# SCH_CarAccessoryKitV1_0_2024-07-24.net
KiCad netlist of a schematic drawn in EasyEDA
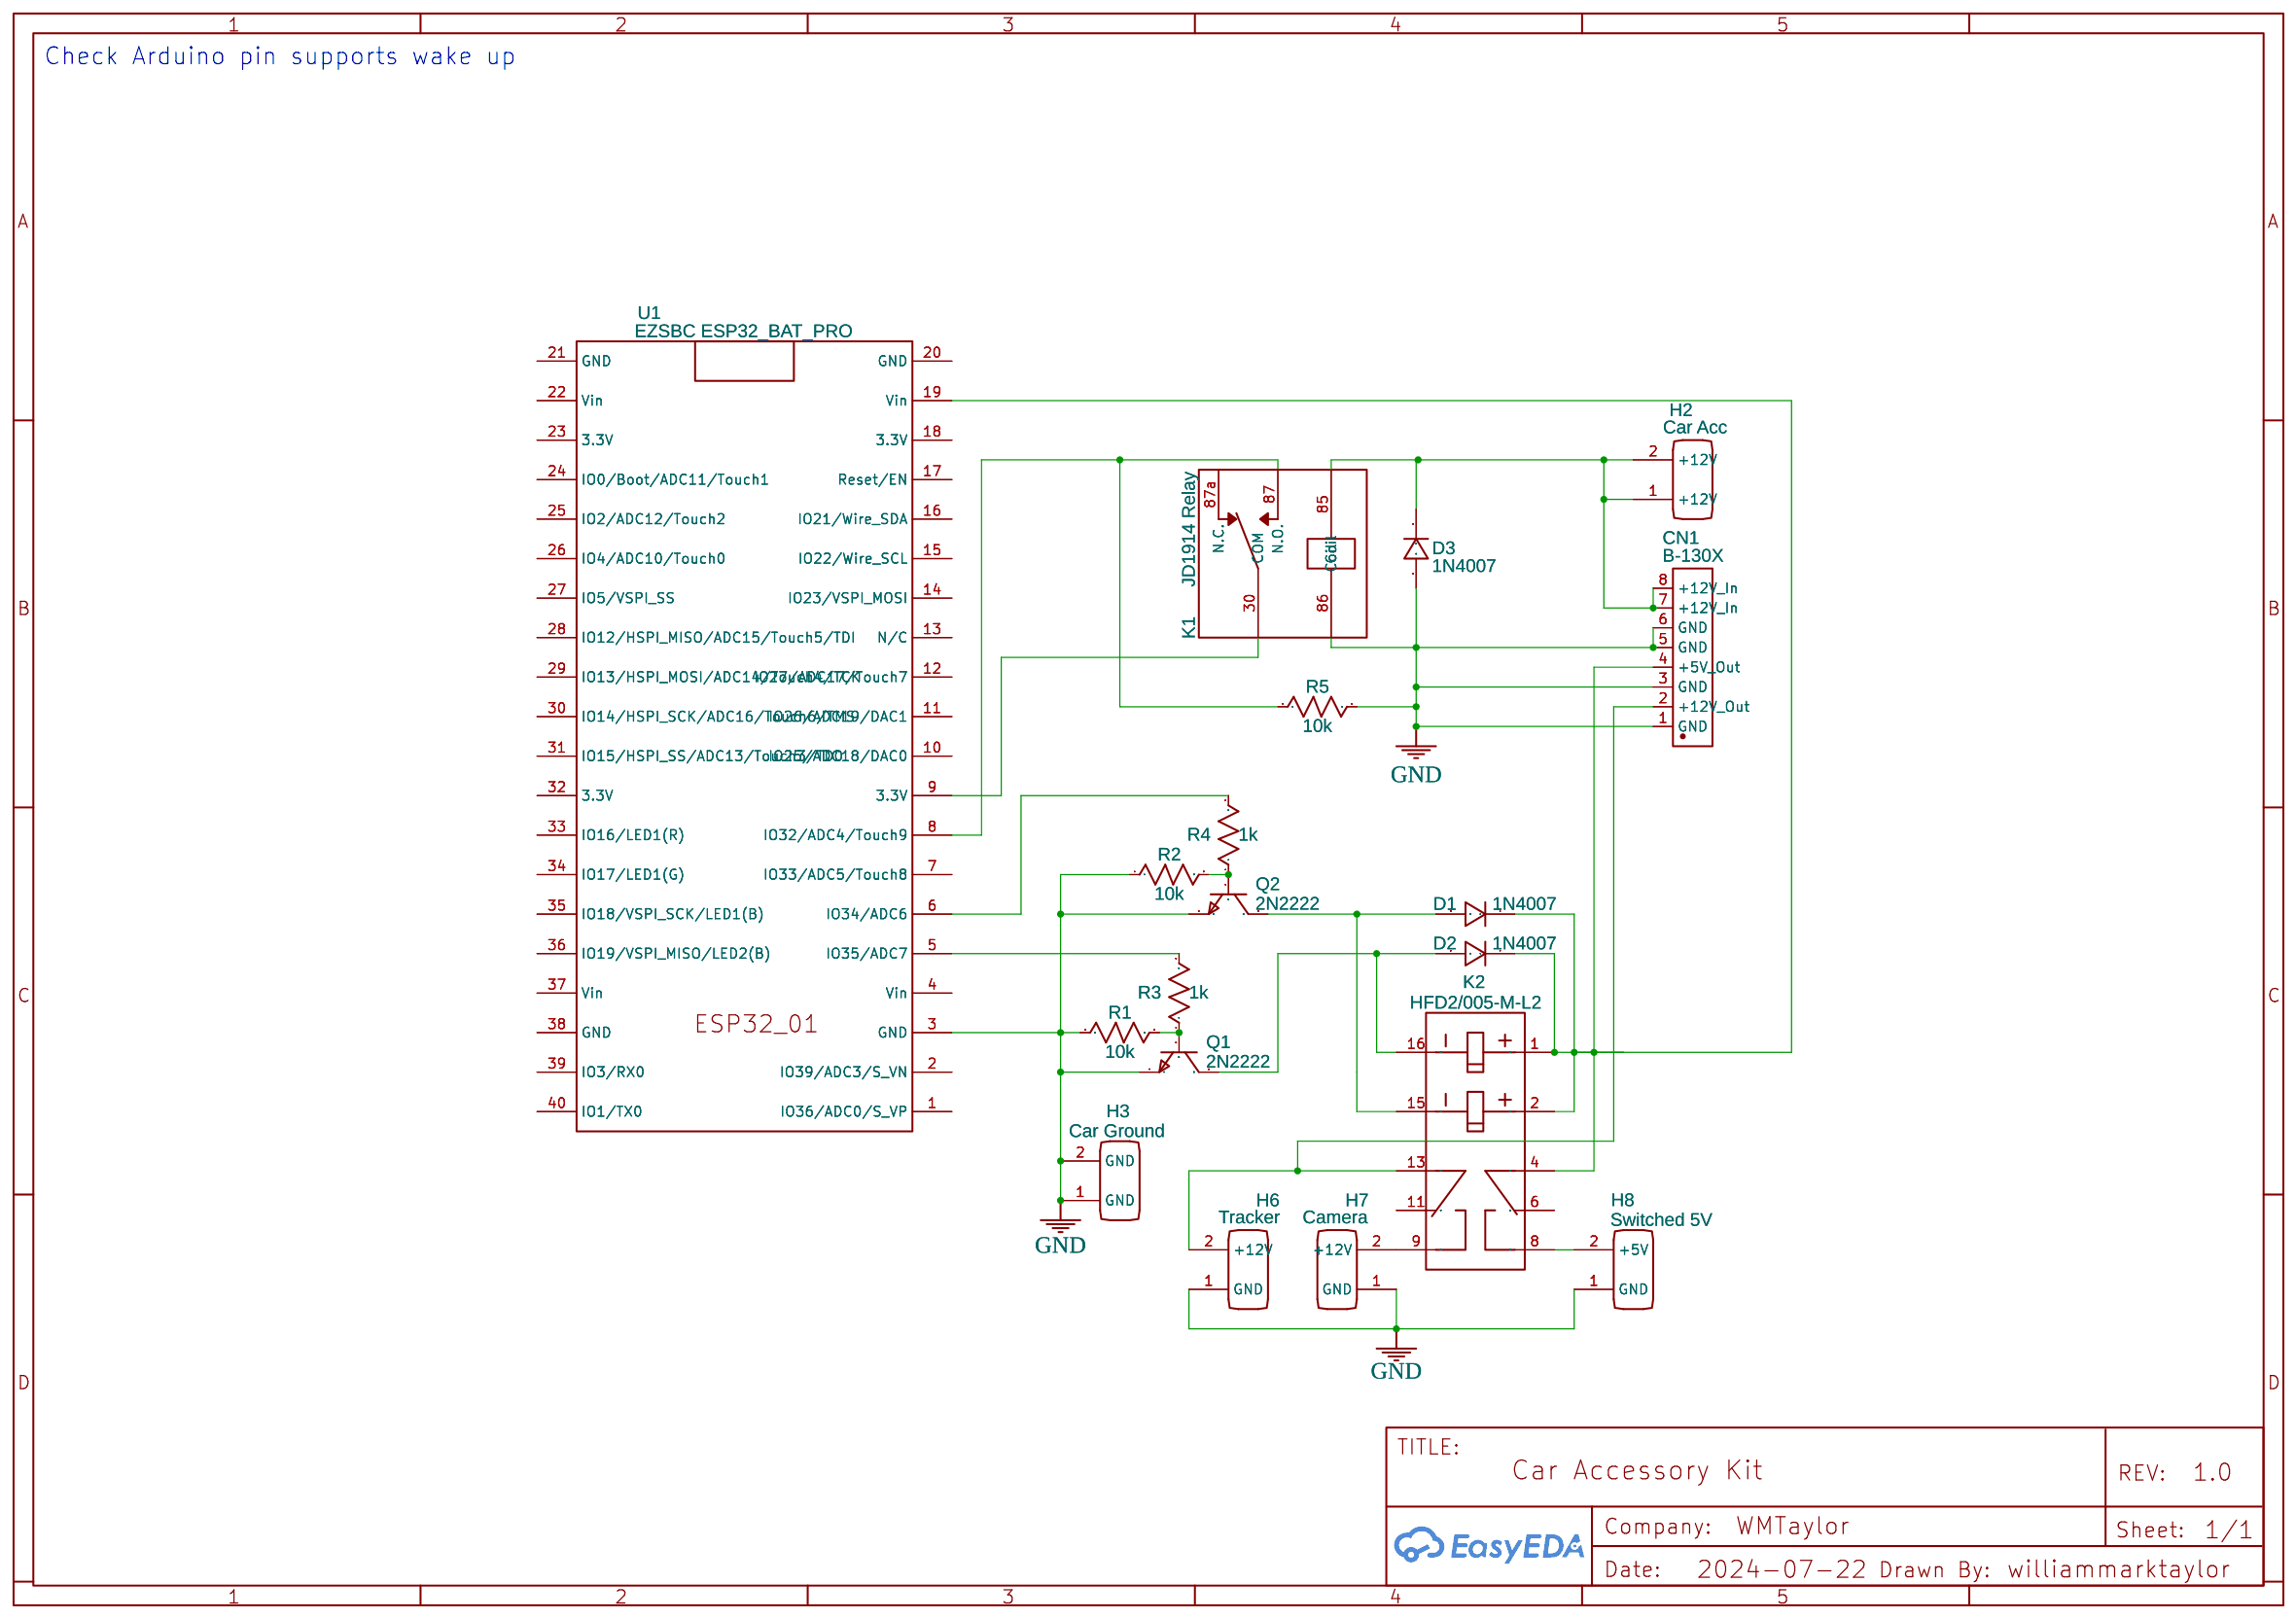
[diagram p0: schematic sheet]

(export (version "E")
  (design (tool "Eeschema 10.0.6"))
  (components
    (comp (ref "CN1")
      (value "B-130X")
      (fields (field (name "Manufacturer Part") "CH3.96-8A") (field (name "Manufacturer") "BOOMELE"))
      (libsource (lib "") (part "CH3.96-8A"))
    )
    (comp (ref "D1")
      (value "1N4007")
      (fields (field (name "Manufacturer") "SEMTECH"))
      (libsource (lib "") (part "1N4007"))
    )
    (comp (ref "D2")
      (value "1N4007")
      (fields (field (name "Manufacturer") "SEMTECH"))
      (libsource (lib "") (part "1N4007"))
    )
    (comp (ref "D3")
      (value "1N4007")
      (fields (field (name "Manufacturer") "SEMTECH"))
      (libsource (lib "") (part "1N4007_1"))
    )
    (comp (ref "H2") (value "Car Acc") (libsource (lib "") (part "JST_VH-2P-3.96")))
    (comp (ref "H3") (value "Car Ground") (libsource (lib "") (part "JST_VH-2P-3.96_1")))
    (comp (ref "H6") (value "Tracker") (libsource (lib "") (part "JST_VH-2P-3.96_3")))
    (comp (ref "H7") (value "Camera") (libsource (lib "") (part "JST_VH-2P-3.96_4")))
    (comp (ref "H8") (value "Switched 5V") (libsource (lib "") (part "JST_VH-2P-3.96_2")))
    (comp (ref "K1")
      (value "JD1914 Relay")
      (fields (field (name "Manufacturer Part") "JD1914") (field (name "Manufacturer") "BenFeng"))
      (libsource (lib "") (part "RELAY JD1914 12V 80A"))
    )
    (comp (ref "K2")
      (value "HFD2/005-M-L2")
      (fields (field (name "Manufacturer") "HF(宏发)"))
      (libsource (lib "") (part "HFD2/005-M-L2"))
    )
    (comp (ref "Q1") (value "2N2222") (libsource (lib "") (part "2N2222")))
    (comp (ref "Q2") (value "2N2222") (libsource (lib "") (part "2N2222")))
    (comp (ref "R1") (value "10k") (libsource (lib "") (part "R_AXIAL-0.3_US")))
    (comp (ref "R2") (value "10k") (libsource (lib "") (part "R_AXIAL-0.3_US")))
    (comp (ref "R3") (value "1k") (libsource (lib "") (part "R_AXIAL-0.3_US_1")))
    (comp (ref "R4") (value "1k") (libsource (lib "") (part "R_AXIAL-0.3_US_1")))
    (comp (ref "R5") (value "10k") (libsource (lib "") (part "R_AXIAL-0.3_US")))
    (comp (ref "U1")
      (value "EZSBC ESP32_BAT_PRO")
      (fields (field (name "Manufacturer Part") "ESP32_01") (field (name "Manufacturer") "EZSBC"))
      (libsource (lib "") (part "EZSBC ESP32_01"))
    )
  )
  (nets
    (net (code "1") (name "GND") (class "Default")
      (node (ref "CN1") (pin "1") (pinfunction "GND_1") (pintype "unspecified"))
      (node (ref "CN1") (pin "3") (pinfunction "GND_3") (pintype "unspecified"))
      (node (ref "CN1") (pin "5") (pinfunction "GND_5") (pintype "unspecified"))
      (node (ref "CN1") (pin "6") (pinfunction "GND_6") (pintype "unspecified"))
      (node (ref "D3") (pin "2") (pinfunction "2_2") (pintype "unspecified"))
      (node (ref "H3") (pin "1") (pinfunction "GND_1") (pintype "unspecified"))
      (node (ref "H3") (pin "2") (pinfunction "GND_2") (pintype "unspecified"))
      (node (ref "H6") (pin "1") (pinfunction "GND_1") (pintype "unspecified"))
      (node (ref "H7") (pin "1") (pinfunction "GND_1") (pintype "unspecified"))
      (node (ref "H8") (pin "1") (pinfunction "GND_1") (pintype "unspecified"))
      (node (ref "K1") (pin "86") (pinfunction "Coil_86") (pintype "unspecified"))
      (node (ref "Q1") (pin "1") (pinfunction "E_1") (pintype "unspecified"))
      (node (ref "Q2") (pin "1") (pinfunction "E_1") (pintype "unspecified"))
      (node (ref "R1") (pin "1") (pinfunction "1_1") (pintype "unspecified"))
      (node (ref "R2") (pin "1") (pinfunction "1_1") (pintype "unspecified"))
      (node (ref "R5") (pin "2") (pinfunction "2_2") (pintype "unspecified"))
      (node (ref "U1") (pin "3") (pinfunction "GND_3") (pintype "unspecified"))
    )
    (net (code "2") (name "Net-(CN1-+5V_Out)") (class "Default")
      (node (ref "CN1") (pin "4") (pinfunction "+5V_Out_4") (pintype "unspecified"))
      (node (ref "D1") (pin "1") (pinfunction "1_1") (pintype "unspecified"))
      (node (ref "D2") (pin "1") (pinfunction "1_1") (pintype "unspecified"))
      (node (ref "K2") (pin "1") (pinfunction "1_1") (pintype "unspecified"))
      (node (ref "K2") (pin "2") (pinfunction "2_2") (pintype "unspecified"))
      (node (ref "K2") (pin "4") (pinfunction "4_4") (pintype "unspecified"))
      (node (ref "U1") (pin "19") (pinfunction "Vin_19") (pintype "unspecified"))
    )
    (net (code "3") (name "Net-(CN1-+12V_In-Pad7)") (class "Default")
      (node (ref "CN1") (pin "7") (pinfunction "+12V_In_7") (pintype "unspecified"))
      (node (ref "CN1") (pin "8") (pinfunction "+12V_In_8") (pintype "unspecified"))
      (node (ref "D3") (pin "1") (pinfunction "1_1") (pintype "unspecified"))
      (node (ref "H2") (pin "1") (pinfunction "+12V_1") (pintype "unspecified"))
      (node (ref "H2") (pin "2") (pinfunction "+12V_2") (pintype "unspecified"))
      (node (ref "K1") (pin "85") (pinfunction "Coil_85") (pintype "unspecified"))
    )
    (net (code "4") (name "Net-(CN1-+12V_Out)") (class "Default")
      (node (ref "CN1") (pin "2") (pinfunction "+12V_Out_2") (pintype "unspecified"))
      (node (ref "H6") (pin "2") (pinfunction "+12V_2") (pintype "unspecified"))
      (node (ref "K2") (pin "13") (pinfunction "13_13") (pintype "unspecified"))
    )
    (net (code "5") (name "Net-(H7-+12V)") (class "Default")
      (node (ref "H7") (pin "2") (pinfunction "+12V_2") (pintype "unspecified"))
      (node (ref "K2") (pin "9") (pinfunction "9_9") (pintype "unspecified"))
    )
    (net (code "6") (name "Net-(H8-+5V)") (class "Default")
      (node (ref "H8") (pin "2") (pinfunction "+5V_2") (pintype "unspecified"))
      (node (ref "K2") (pin "8") (pinfunction "8_8") (pintype "unspecified"))
    )
    (net (code "7") (name "Net-(K1-COM)") (class "Default")
      (node (ref "K1") (pin "30") (pinfunction "COM_30") (pintype "unspecified"))
      (node (ref "U1") (pin "9") (pinfunction "3.3V_9") (pintype "unspecified"))
    )
    (net (code "8") (name "Net-(K1-N.O.)") (class "Default")
      (node (ref "K1") (pin "87") (pinfunction "N.O._87") (pintype "unspecified"))
      (node (ref "R5") (pin "1") (pinfunction "1_1") (pintype "unspecified"))
      (node (ref "U1") (pin "8") (pinfunction "IO32/ADC4/Touch9_8") (pintype "unspecified"))
    )
    (net (code "9") (name "Net-(Q1-B)") (class "Default")
      (node (ref "Q1") (pin "2") (pinfunction "B_2") (pintype "unspecified"))
      (node (ref "R1") (pin "2") (pinfunction "2_2") (pintype "unspecified"))
      (node (ref "R3") (pin "1") (pinfunction "1_1") (pintype "unspecified"))
    )
    (net (code "10") (name "Net-(Q1-C)") (class "Default")
      (node (ref "D2") (pin "2") (pinfunction "2_2") (pintype "unspecified"))
      (node (ref "K2") (pin "16") (pinfunction "16_16") (pintype "unspecified"))
      (node (ref "Q1") (pin "3") (pinfunction "C_3") (pintype "unspecified"))
    )
    (net (code "11") (name "Net-(Q2-B)") (class "Default")
      (node (ref "Q2") (pin "2") (pinfunction "B_2") (pintype "unspecified"))
      (node (ref "R2") (pin "2") (pinfunction "2_2") (pintype "unspecified"))
      (node (ref "R4") (pin "1") (pinfunction "1_1") (pintype "unspecified"))
    )
    (net (code "12") (name "Net-(Q2-C)") (class "Default")
      (node (ref "D1") (pin "2") (pinfunction "2_2") (pintype "unspecified"))
      (node (ref "K2") (pin "15") (pinfunction "15_15") (pintype "unspecified"))
      (node (ref "Q2") (pin "3") (pinfunction "C_3") (pintype "unspecified"))
    )
    (net (code "13") (name "Net-(U1-IO34{slash}ADC6)") (class "Default")
      (node (ref "R4") (pin "2") (pinfunction "2_2") (pintype "unspecified"))
      (node (ref "U1") (pin "6") (pinfunction "IO34/ADC6_6") (pintype "unspecified"))
    )
    (net (code "14") (name "Net-(U1-IO35{slash}ADC7)") (class "Default")
      (node (ref "R3") (pin "2") (pinfunction "2_2") (pintype "unspecified"))
      (node (ref "U1") (pin "5") (pinfunction "IO35/ADC7_5") (pintype "unspecified"))
    )
    (net (code "15") (name "unconnected-(K1-N.C.-Pad87a)") (class "Default")
      (node (ref "K1") (pin "87a") (pinfunction "N.C._87a") (pintype "unspecified"))
    )
    (net (code "16") (name "unconnected-(K2-Pad6)") (class "Default")
      (node (ref "K2") (pin "6") (pinfunction "6_6") (pintype "unspecified"))
    )
    (net (code "17") (name "unconnected-(K2-Pad11)") (class "Default")
      (node (ref "K2") (pin "11") (pinfunction "11_11") (pintype "unspecified"))
    )
    (net (code "18") (name "unconnected-(U1-3.3V-Pad18)") (class "Default")
      (node (ref "U1") (pin "18") (pinfunction "3.3V_18") (pintype "unspecified"))
    )
    (net (code "19") (name "unconnected-(U1-3.3V-Pad23)") (class "Default")
      (node (ref "U1") (pin "23") (pinfunction "3.3V_23") (pintype "unspecified"))
    )
    (net (code "20") (name "unconnected-(U1-3.3V-Pad32)") (class "Default")
      (node (ref "U1") (pin "32") (pinfunction "3.3V_32") (pintype "unspecified"))
    )
    (net (code "21") (name "unconnected-(U1-GND-Pad20)") (class "Default")
      (node (ref "U1") (pin "20") (pinfunction "GND_20") (pintype "unspecified"))
    )
    (net (code "22") (name "unconnected-(U1-GND-Pad21)") (class "Default")
      (node (ref "U1") (pin "21") (pinfunction "GND_21") (pintype "unspecified"))
    )
    (net (code "23") (name "unconnected-(U1-GND-Pad38)") (class "Default")
      (node (ref "U1") (pin "38") (pinfunction "GND_38") (pintype "unspecified"))
    )
    (net (code "24") (name "unconnected-(U1-IO0{slash}Boot{slash}ADC11{slash}Touch1-Pad24)") (class "Default")
      (node (ref "U1") (pin "24") (pinfunction "IO0/Boot/ADC11/Touch1_24") (pintype "unspecified"))
    )
    (net (code "25") (name "unconnected-(U1-IO1{slash}TX0-Pad40)") (class "Default")
      (node (ref "U1") (pin "40") (pinfunction "IO1/TX0_40") (pintype "unspecified"))
    )
    (net (code "26") (name "unconnected-(U1-IO2{slash}ADC12{slash}Touch2-Pad25)") (class "Default")
      (node (ref "U1") (pin "25") (pinfunction "IO2/ADC12/Touch2_25") (pintype "unspecified"))
    )
    (net (code "27") (name "unconnected-(U1-IO3{slash}RX0-Pad39)") (class "Default")
      (node (ref "U1") (pin "39") (pinfunction "IO3/RX0_39") (pintype "unspecified"))
    )
    (net (code "28") (name "unconnected-(U1-IO4{slash}ADC10{slash}Touch0-Pad26)") (class "Default")
      (node (ref "U1") (pin "26") (pinfunction "IO4/ADC10/Touch0_26") (pintype "unspecified"))
    )
    (net (code "29") (name "unconnected-(U1-IO5{slash}VSPI_SS-Pad27)") (class "Default")
      (node (ref "U1") (pin "27") (pinfunction "IO5/VSPI_SS_27") (pintype "unspecified"))
    )
    (net (code "30") (name "unconnected-(U1-IO12{slash}HSPI_MISO{slash}ADC15{slash}Touch5{slash}TDI-Pad28)") (class "Default")
      (node (ref "U1") (pin "28") (pinfunction "IO12/HSPI_MISO/ADC15/Touch5/TDI_28") (pintype "unspecified"))
    )
    (net (code "31") (name "unconnected-(U1-IO13{slash}HSPI_MOSI{slash}ADC14{slash}Touch4{slash}TCK-Pad29)") (class "Default")
      (node (ref "U1") (pin "29") (pinfunction "IO13/HSPI_MOSI/ADC14/Touch4/TCK_29") (pintype "unspecified"))
    )
    (net (code "32") (name "unconnected-(U1-IO14{slash}HSPI_SCK{slash}ADC16{slash}Touch6{slash}TMS-Pad30)") (class "Default")
      (node (ref "U1") (pin "30") (pinfunction "IO14/HSPI_SCK/ADC16/Touch6/TMS_30") (pintype "unspecified"))
    )
    (net (code "33") (name "unconnected-(U1-IO15{slash}HSPI_SS{slash}ADC13{slash}Touch3{slash}TD0-Pad31)") (class "Default")
      (node (ref "U1") (pin "31") (pinfunction "IO15/HSPI_SS/ADC13/Touch3/TD0_31") (pintype "unspecified"))
    )
    (net (code "34") (name "unconnected-(U1-IO16{slash}LED1(R)-Pad33)") (class "Default")
      (node (ref "U1") (pin "33") (pinfunction "IO16/LED1(R)_33") (pintype "unspecified"))
    )
    (net (code "35") (name "unconnected-(U1-IO17{slash}LED1(G)-Pad34)") (class "Default")
      (node (ref "U1") (pin "34") (pinfunction "IO17/LED1(G)_34") (pintype "unspecified"))
    )
    (net (code "36") (name "unconnected-(U1-IO18{slash}VSPI_SCK{slash}LED1(B)-Pad35)") (class "Default")
      (node (ref "U1") (pin "35") (pinfunction "IO18/VSPI_SCK/LED1(B)_35") (pintype "unspecified"))
    )
    (net (code "37") (name "unconnected-(U1-IO19{slash}VSPI_MISO{slash}LED2(B)-Pad36)") (class "Default")
      (node (ref "U1") (pin "36") (pinfunction "IO19/VSPI_MISO/LED2(B)_36") (pintype "unspecified"))
    )
    (net (code "38") (name "unconnected-(U1-IO21{slash}Wire_SDA-Pad16)") (class "Default")
      (node (ref "U1") (pin "16") (pinfunction "IO21/Wire_SDA_16") (pintype "unspecified"))
    )
    (net (code "39") (name "unconnected-(U1-IO22{slash}Wire_SCL-Pad15)") (class "Default")
      (node (ref "U1") (pin "15") (pinfunction "IO22/Wire_SCL_15") (pintype "unspecified"))
    )
    (net (code "40") (name "unconnected-(U1-IO23{slash}VSPI_MOSI-Pad14)") (class "Default")
      (node (ref "U1") (pin "14") (pinfunction "IO23/VSPI_MOSI_14") (pintype "unspecified"))
    )
    (net (code "41") (name "unconnected-(U1-IO25{slash}ADC18{slash}DAC0-Pad10)") (class "Default")
      (node (ref "U1") (pin "10") (pinfunction "IO25/ADC18/DAC0_10") (pintype "unspecified"))
    )
    (net (code "42") (name "unconnected-(U1-IO26{slash}ADC19{slash}DAC1-Pad11)") (class "Default")
      (node (ref "U1") (pin "11") (pinfunction "IO26/ADC19/DAC1_11") (pintype "unspecified"))
    )
    (net (code "43") (name "unconnected-(U1-IO27{slash}ADC17{slash}Touch7-Pad12)") (class "Default")
      (node (ref "U1") (pin "12") (pinfunction "IO27/ADC17/Touch7_12") (pintype "unspecified"))
    )
    (net (code "44") (name "unconnected-(U1-IO33{slash}ADC5{slash}Touch8-Pad7)") (class "Default")
      (node (ref "U1") (pin "7") (pinfunction "IO33/ADC5/Touch8_7") (pintype "unspecified"))
    )
    (net (code "45") (name "unconnected-(U1-IO36{slash}ADC0{slash}S_VP-Pad1)") (class "Default")
      (node (ref "U1") (pin "1") (pinfunction "IO36/ADC0/S_VP_1") (pintype "unspecified"))
    )
    (net (code "46") (name "unconnected-(U1-IO39{slash}ADC3{slash}S_VN-Pad2)") (class "Default")
      (node (ref "U1") (pin "2") (pinfunction "IO39/ADC3/S_VN_2") (pintype "unspecified"))
    )
    (net (code "47") (name "unconnected-(U1-N{slash}C-Pad13)") (class "Default")
      (node (ref "U1") (pin "13") (pinfunction "N/C_13") (pintype "unspecified"))
    )
    (net (code "48") (name "unconnected-(U1-Reset{slash}EN-Pad17)") (class "Default")
      (node (ref "U1") (pin "17") (pinfunction "Reset/EN_17") (pintype "unspecified"))
    )
    (net (code "49") (name "unconnected-(U1-Vin-Pad4)") (class "Default")
      (node (ref "U1") (pin "4") (pinfunction "Vin_4") (pintype "unspecified"))
    )
    (net (code "50") (name "unconnected-(U1-Vin-Pad22)") (class "Default")
      (node (ref "U1") (pin "22") (pinfunction "Vin_22") (pintype "unspecified"))
    )
    (net (code "51") (name "unconnected-(U1-Vin-Pad37)") (class "Default")
      (node (ref "U1") (pin "37") (pinfunction "Vin_37") (pintype "unspecified"))
    )
  )
)
